# tm7_revB.net
KiCad netlist of a schematic drawn in EAGLE
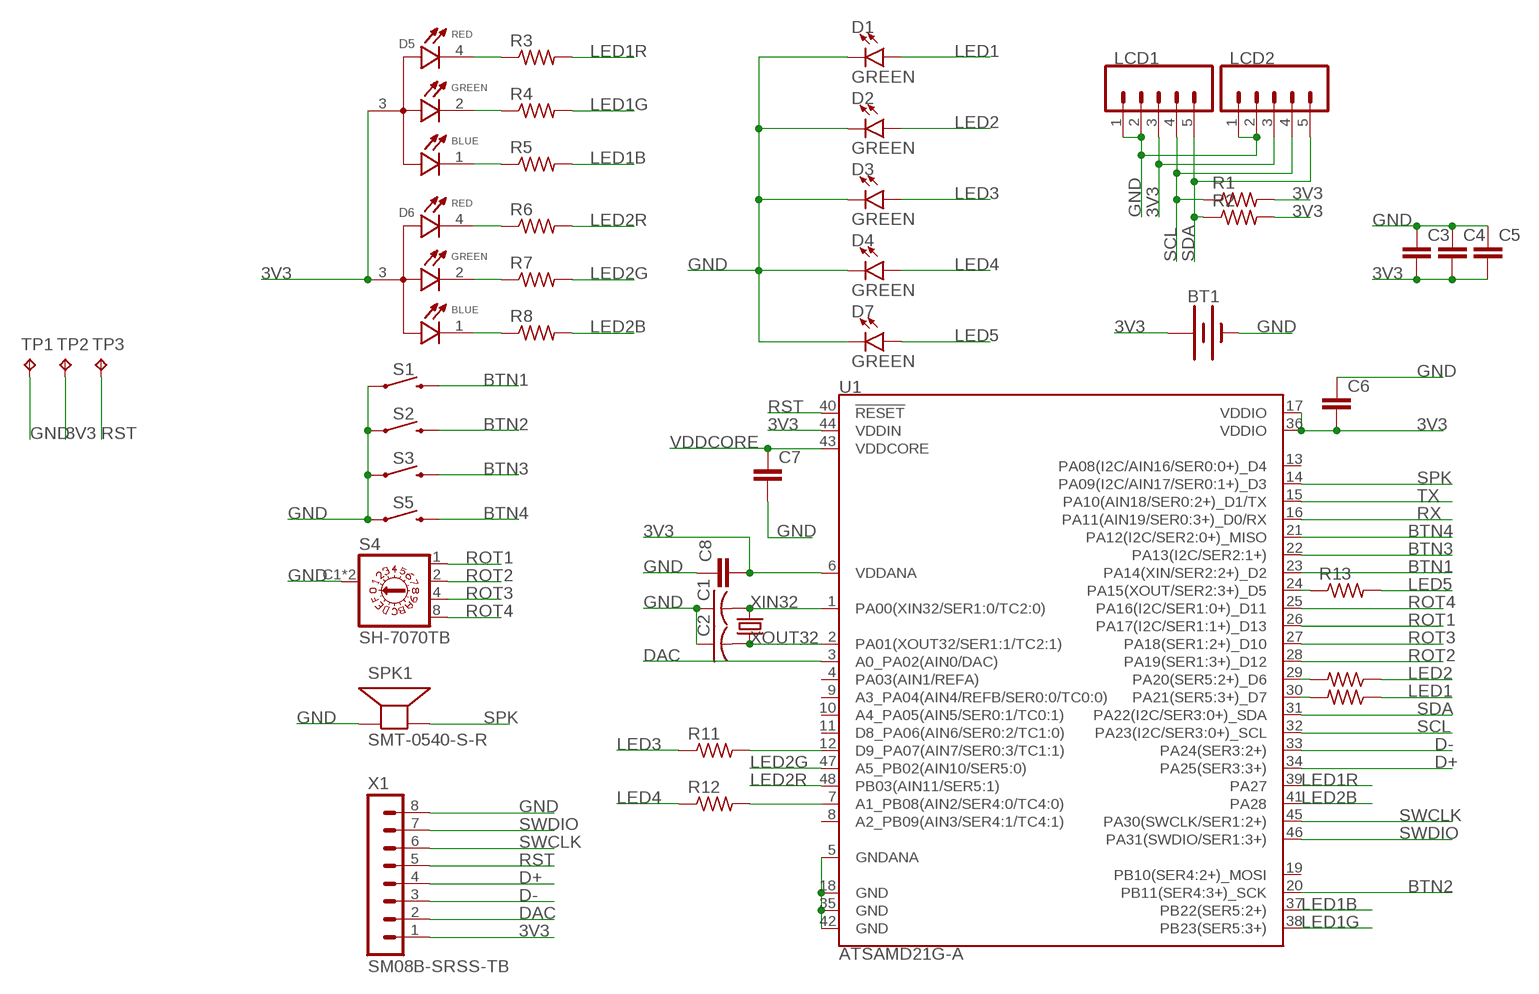
[diagram p0: schematic, sheet 1]

(export (version "E")
  (design (tool "Eeschema 10.0.6"))
  (components
    (comp (ref "BT1")
      (value "BATTERY-20MM_SMD_4LEGS_OVERPASTE_INNER")
      (footprint "eagle-import:BATTCON_20MM_4LEGS_OVERPASTE_INNER")
      (libsource (lib "eagle-import") (part "BATTERY-20MM_SMD_4LEGS_OVERPASTE_INNER"))
    )
    (comp (ref "C1")
      (value "C-USC0603")
      (footprint "eagle-import:C0603")
      (libsource (lib "eagle-import") (part "C-USC0603"))
    )
    (comp (ref "C2")
      (value "C-USC0603")
      (footprint "eagle-import:C0603")
      (libsource (lib "eagle-import") (part "C-USC0603"))
    )
    (comp (ref "C3")
      (value "C-EUC0603")
      (footprint "eagle-import:C0603")
      (libsource (lib "eagle-import") (part "C-EUC0603"))
    )
    (comp (ref "C4")
      (value "C-EUC0603")
      (footprint "eagle-import:C0603")
      (libsource (lib "eagle-import") (part "C-EUC0603"))
    )
    (comp (ref "C5")
      (value "C-EUC0603")
      (footprint "eagle-import:C0603")
      (libsource (lib "eagle-import") (part "C-EUC0603"))
    )
    (comp (ref "C6")
      (value "C-EUC0603")
      (footprint "eagle-import:C0603")
      (libsource (lib "eagle-import") (part "C-EUC0603"))
    )
    (comp (ref "C7")
      (value "C-EUC0603")
      (footprint "eagle-import:C0603")
      (libsource (lib "eagle-import") (part "C-EUC0603"))
    )
    (comp (ref "C8")
      (value "C-EUC0603")
      (footprint "eagle-import:C0603")
      (libsource (lib "eagle-import") (part "C-EUC0603"))
    )
    (comp (ref "D1")
      (value "GREEN")
      (footprint "eagle-import:LED-1206")
      (libsource (lib "eagle-import") (part "LED-GREEN1206"))
    )
    (comp (ref "D2")
      (value "GREEN")
      (footprint "eagle-import:LED-1206")
      (libsource (lib "eagle-import") (part "LED-GREEN1206"))
    )
    (comp (ref "D3")
      (value "GREEN")
      (footprint "eagle-import:LED-1206")
      (libsource (lib "eagle-import") (part "LED-GREEN1206"))
    )
    (comp (ref "D4")
      (value "GREEN")
      (footprint "eagle-import:LED-1206")
      (libsource (lib "eagle-import") (part "LED-GREEN1206"))
    )
    (comp (ref "D5")
      (value "EAST1616RGBA3")
      (footprint "eagle-import:LED_EAST1616RGBA3")
      (fields (field (name "MF") "Everlight Electronics"))
      (libsource (lib "eagle-import") (part "EAST1616RGBA3"))
    )
    (comp (ref "D6")
      (value "EAST1616RGBA3")
      (footprint "eagle-import:LED_EAST1616RGBA3")
      (fields (field (name "MF") "Everlight Electronics"))
      (libsource (lib "eagle-import") (part "EAST1616RGBA3"))
    )
    (comp (ref "D7")
      (value "GREEN")
      (footprint "eagle-import:LED-1206")
      (libsource (lib "eagle-import") (part "LED-GREEN1206"))
    )
    (comp (ref "LCD1")
      (value "CONN_05VERT_FEMALE_HEADER")
      (footprint "eagle-import:1X05_SMD_VERTICAL_COMBO")
      (libsource (lib "eagle-import") (part "CONN_05VERT_FEMALE_HEADER"))
    )
    (comp (ref "LCD2")
      (value "CONN_05VERT_FEMALE_HEADER")
      (footprint "eagle-import:1X05_SMD_VERTICAL_COMBO")
      (libsource (lib "eagle-import") (part "CONN_05VERT_FEMALE_HEADER"))
    )
    (comp (ref "R1")
      (value "R-US_R0603")
      (footprint "eagle-import:R0603")
      (libsource (lib "eagle-import") (part "R-US_R0603"))
    )
    (comp (ref "R2")
      (value "R-US_R0603")
      (footprint "eagle-import:R0603")
      (libsource (lib "eagle-import") (part "R-US_R0603"))
    )
    (comp (ref "R3")
      (value "R-US_R0603")
      (footprint "eagle-import:R0603")
      (libsource (lib "eagle-import") (part "R-US_R0603"))
    )
    (comp (ref "R4")
      (value "R-US_R0603")
      (footprint "eagle-import:R0603")
      (libsource (lib "eagle-import") (part "R-US_R0603"))
    )
    (comp (ref "R5")
      (value "R-US_R0603")
      (footprint "eagle-import:R0603")
      (libsource (lib "eagle-import") (part "R-US_R0603"))
    )
    (comp (ref "R6")
      (value "R-US_R0603")
      (footprint "eagle-import:R0603")
      (libsource (lib "eagle-import") (part "R-US_R0603"))
    )
    (comp (ref "R7")
      (value "R-US_R0603")
      (footprint "eagle-import:R0603")
      (libsource (lib "eagle-import") (part "R-US_R0603"))
    )
    (comp (ref "R8")
      (value "R-US_R0603")
      (footprint "eagle-import:R0603")
      (libsource (lib "eagle-import") (part "R-US_R0603"))
    )
    (comp (ref "R9")
      (value "R-US_R0603")
      (footprint "eagle-import:R0603")
      (libsource (lib "eagle-import") (part "R-US_R0603"))
    )
    (comp (ref "R10")
      (value "R-US_R0603")
      (footprint "eagle-import:R0603")
      (libsource (lib "eagle-import") (part "R-US_R0603"))
    )
    (comp (ref "R11")
      (value "R-US_R0603")
      (footprint "eagle-import:R0603")
      (libsource (lib "eagle-import") (part "R-US_R0603"))
    )
    (comp (ref "R12")
      (value "R-US_R0603")
      (footprint "eagle-import:R0603")
      (libsource (lib "eagle-import") (part "R-US_R0603"))
    )
    (comp (ref "R13")
      (value "R-US_R0603")
      (footprint "eagle-import:R0603")
      (libsource (lib "eagle-import") (part "R-US_R0603"))
    )
    (comp (ref "S1")
      (value "MOMENTARY-SWITCH-SPST-SMD-6.0X3.5MM")
      (footprint "eagle-import:TACTILE_SWITCH_SMD_6.0X3.5MM")
      (libsource (lib "eagle-import") (part "MOMENTARY-SWITCH-SPST-SMD-6.0X3.5MM"))
    )
    (comp (ref "S2")
      (value "MOMENTARY-SWITCH-SPST-SMD-6.0X3.5MM")
      (footprint "eagle-import:TACTILE_SWITCH_SMD_6.0X3.5MM")
      (libsource (lib "eagle-import") (part "MOMENTARY-SWITCH-SPST-SMD-6.0X3.5MM"))
    )
    (comp (ref "S3")
      (value "MOMENTARY-SWITCH-SPST-SMD-6.0X3.5MM")
      (footprint "eagle-import:TACTILE_SWITCH_SMD_6.0X3.5MM")
      (libsource (lib "eagle-import") (part "MOMENTARY-SWITCH-SPST-SMD-6.0X3.5MM"))
    )
    (comp (ref "S4")
      (value "SH-7070TB")
      (footprint "eagle-import:SH-7070B")
      (fields (field (name "MF") "Nidec Copal"))
      (libsource (lib "eagle-import") (part "SH-7070TB"))
    )
    (comp (ref "S5")
      (value "MOMENTARY-SWITCH-SPST-SMD-6.0X3.5MM")
      (footprint "eagle-import:TACTILE_SWITCH_SMD_6.0X3.5MM")
      (libsource (lib "eagle-import") (part "MOMENTARY-SWITCH-SPST-SMD-6.0X3.5MM"))
    )
    (comp (ref "SPK1")
      (value "SMT-0540-S-R")
      (footprint "eagle-import:SMT-0540-S-R")
      (fields (field (name "MF") "PUI"))
      (libsource (lib "eagle-import") (part "SMT-0540-S-R"))
    )
    (comp (ref "TP1")
      (value "TPTP12R")
      (footprint "eagle-import:TP12R")
      (libsource (lib "eagle-import") (part "TPTP12R"))
    )
    (comp (ref "TP2")
      (value "TPTP12R")
      (footprint "eagle-import:TP12R")
      (libsource (lib "eagle-import") (part "TPTP12R"))
    )
    (comp (ref "TP3")
      (value "TPTP12R")
      (footprint "eagle-import:TP12R")
      (libsource (lib "eagle-import") (part "TPTP12R"))
    )
    (comp (ref "U1")
      (value "ATSAMD21G-A")
      (footprint "eagle-import:TQFP-48")
      (libsource (lib "eagle-import") (part "ATSAMD21G-A"))
    )
    (comp (ref "X1")
      (value "SM08B-SRSS-TB")
      (footprint "eagle-import:SM08B-SRSS-TB")
      (libsource (lib "eagle-import") (part "SM08B-SRSS-TB"))
    )
    (comp (ref "Y1")
      (value "32.768kHz")
      (footprint "eagle-import:CRYSTAL-SMD-3.2X1.5MM")
      (libsource (lib "eagle-import") (part "CRYSTAL-32.768KHZSMD-3.2X1.5"))
    )
  )
  (nets
    (net (code "1") (name "/3V3") (class "Default")
      (node (ref "BT1") (pin "1") (pinfunction "+_1") (pintype "power_in"))
      (node (ref "C3") (pin "2") (pinfunction "2_2") (pintype "passive"))
      (node (ref "C4") (pin "2") (pinfunction "2_2") (pintype "passive"))
      (node (ref "C5") (pin "2") (pinfunction "2_2") (pintype "passive"))
      (node (ref "C6") (pin "2") (pinfunction "2_2") (pintype "passive"))
      (node (ref "C8") (pin "2") (pinfunction "2_2") (pintype "passive"))
      (node (ref "D5") (pin "3") (pinfunction "A_3") (pintype "passive"))
      (node (ref "D6") (pin "3") (pinfunction "A_3") (pintype "passive"))
      (node (ref "LCD1") (pin "3") (pinfunction "3_3") (pintype "passive"))
      (node (ref "LCD2") (pin "3") (pinfunction "3_3") (pintype "passive"))
      (node (ref "R1") (pin "2") (pinfunction "2_2") (pintype "passive"))
      (node (ref "R2") (pin "2") (pinfunction "2_2") (pintype "passive"))
      (node (ref "TP2") (pin "TP") (pinfunction "TP_TP") (pintype "input"))
      (node (ref "U1") (pin "17") (pinfunction "VDDIO_17") (pintype "bidirectional"))
      (node (ref "U1") (pin "36") (pinfunction "VDDIO_36") (pintype "bidirectional"))
      (node (ref "U1") (pin "44") (pinfunction "VDDIN_44") (pintype "bidirectional"))
      (node (ref "U1") (pin "6") (pinfunction "VDDANA_6") (pintype "bidirectional"))
      (node (ref "X1") (pin "1") (pinfunction "1_1") (pintype "passive"))
    )
    (net (code "2") (name "/BTN1") (class "Default")
      (node (ref "S1") (pin "2") (pinfunction "2_2") (pintype "passive"))
      (node (ref "U1") (pin "23") (pinfunction "PA14(XIN/SER2:2+)_D2_23") (pintype "bidirectional"))
    )
    (net (code "3") (name "/BTN2") (class "Default")
      (node (ref "S2") (pin "2") (pinfunction "2_2") (pintype "passive"))
      (node (ref "U1") (pin "20") (pinfunction "PB11(SER4:3+)_SCK_20") (pintype "bidirectional"))
    )
    (net (code "4") (name "/BTN3") (class "Default")
      (node (ref "S3") (pin "2") (pinfunction "2_2") (pintype "passive"))
      (node (ref "U1") (pin "22") (pinfunction "PA13(I2C/SER2:1+)_22") (pintype "bidirectional"))
    )
    (net (code "5") (name "/BTN4") (class "Default")
      (node (ref "S5") (pin "2") (pinfunction "2_2") (pintype "passive"))
      (node (ref "U1") (pin "21") (pinfunction "PA12(I2C/SER2:0+)_MISO_21") (pintype "bidirectional"))
    )
    (net (code "6") (name "/D+") (class "Default")
      (node (ref "U1") (pin "34") (pinfunction "PA25(SER3:3+)_34") (pintype "bidirectional"))
      (node (ref "X1") (pin "4") (pinfunction "4_4") (pintype "passive"))
    )
    (net (code "7") (name "/D-") (class "Default")
      (node (ref "U1") (pin "33") (pinfunction "PA24(SER3:2+)_33") (pintype "bidirectional"))
      (node (ref "X1") (pin "3") (pinfunction "3_3") (pintype "passive"))
    )
    (net (code "8") (name "/DAC") (class "Default")
      (node (ref "U1") (pin "3") (pinfunction "A0_PA02(AIN0/DAC)_3") (pintype "bidirectional"))
      (node (ref "X1") (pin "2") (pinfunction "2_2") (pintype "passive"))
    )
    (net (code "9") (name "/GND") (class "Default")
      (node (ref "BT1") (pin "2") (pinfunction "-_2") (pintype "power_in"))
      (node (ref "C1") (pin "1") (pinfunction "1_1") (pintype "passive"))
      (node (ref "C2") (pin "1") (pinfunction "1_1") (pintype "passive"))
      (node (ref "C3") (pin "1") (pinfunction "1_1") (pintype "passive"))
      (node (ref "C4") (pin "1") (pinfunction "1_1") (pintype "passive"))
      (node (ref "C5") (pin "1") (pinfunction "1_1") (pintype "passive"))
      (node (ref "C6") (pin "1") (pinfunction "1_1") (pintype "passive"))
      (node (ref "C7") (pin "2") (pinfunction "2_2") (pintype "passive"))
      (node (ref "C8") (pin "1") (pinfunction "1_1") (pintype "passive"))
      (node (ref "D1") (pin "C") (pinfunction "C_C") (pintype "passive"))
      (node (ref "D2") (pin "C") (pinfunction "C_C") (pintype "passive"))
      (node (ref "D3") (pin "C") (pinfunction "C_C") (pintype "passive"))
      (node (ref "D4") (pin "C") (pinfunction "C_C") (pintype "passive"))
      (node (ref "D7") (pin "C") (pinfunction "C_C") (pintype "passive"))
      (node (ref "LCD1") (pin "1") (pinfunction "1_1") (pintype "passive"))
      (node (ref "LCD1") (pin "2") (pinfunction "2_2") (pintype "passive"))
      (node (ref "LCD2") (pin "1") (pinfunction "1_1") (pintype "passive"))
      (node (ref "LCD2") (pin "2") (pinfunction "2_2") (pintype "passive"))
      (node (ref "S1") (pin "1") (pinfunction "1_1") (pintype "passive"))
      (node (ref "S2") (pin "1") (pinfunction "1_1") (pintype "passive"))
      (node (ref "S3") (pin "1") (pinfunction "1_1") (pintype "passive"))
      (node (ref "S4") (pin "C1") (pinfunction "C_C1") (pintype "passive"))
      (node (ref "S4") (pin "C2") (pinfunction "C_C2") (pintype "passive"))
      (node (ref "S5") (pin "1") (pinfunction "1_1") (pintype "passive"))
      (node (ref "SPK1") (pin "-") (pinfunction "+_-") (pintype "passive"))
      (node (ref "TP1") (pin "TP") (pinfunction "TP_TP") (pintype "input"))
      (node (ref "U1") (pin "18") (pinfunction "GND_18") (pintype "bidirectional"))
      (node (ref "U1") (pin "35") (pinfunction "GND_35") (pintype "bidirectional"))
      (node (ref "U1") (pin "42") (pinfunction "GND_42") (pintype "bidirectional"))
      (node (ref "U1") (pin "5") (pinfunction "GNDANA_5") (pintype "bidirectional"))
      (node (ref "X1") (pin "8") (pinfunction "8_8") (pintype "passive"))
    )
    (net (code "10") (name "/LED1") (class "Default")
      (node (ref "D1") (pin "A") (pinfunction "A_A") (pintype "passive"))
      (node (ref "R9") (pin "1") (pinfunction "1_1") (pintype "passive"))
    )
    (net (code "11") (name "/LED1B") (class "Default")
      (node (ref "R5") (pin "2") (pinfunction "2_2") (pintype "passive"))
      (node (ref "U1") (pin "37") (pinfunction "PB22(SER5:2+)_37") (pintype "bidirectional"))
    )
    (net (code "12") (name "/LED1G") (class "Default")
      (node (ref "R4") (pin "2") (pinfunction "2_2") (pintype "passive"))
      (node (ref "U1") (pin "38") (pinfunction "PB23(SER5:3+)_38") (pintype "bidirectional"))
    )
    (net (code "13") (name "/LED1R") (class "Default")
      (node (ref "R3") (pin "2") (pinfunction "2_2") (pintype "passive"))
      (node (ref "U1") (pin "39") (pinfunction "PA27_39") (pintype "bidirectional"))
    )
    (net (code "14") (name "/LED2") (class "Default")
      (node (ref "D2") (pin "A") (pinfunction "A_A") (pintype "passive"))
      (node (ref "R10") (pin "1") (pinfunction "1_1") (pintype "passive"))
    )
    (net (code "15") (name "/LED2B") (class "Default")
      (node (ref "R8") (pin "2") (pinfunction "2_2") (pintype "passive"))
      (node (ref "U1") (pin "41") (pinfunction "PA28_41") (pintype "bidirectional"))
    )
    (net (code "16") (name "/LED2G") (class "Default")
      (node (ref "R7") (pin "2") (pinfunction "2_2") (pintype "passive"))
      (node (ref "U1") (pin "47") (pinfunction "A5_PB02(AIN10/SER5:0)_47") (pintype "bidirectional"))
    )
    (net (code "17") (name "/LED2R") (class "Default")
      (node (ref "R6") (pin "2") (pinfunction "2_2") (pintype "passive"))
      (node (ref "U1") (pin "48") (pinfunction "PB03(AIN11/SER5:1)_48") (pintype "bidirectional"))
    )
    (net (code "18") (name "/LED3") (class "Default")
      (node (ref "D3") (pin "A") (pinfunction "A_A") (pintype "passive"))
      (node (ref "R11") (pin "1") (pinfunction "1_1") (pintype "passive"))
    )
    (net (code "19") (name "/LED4") (class "Default")
      (node (ref "D4") (pin "A") (pinfunction "A_A") (pintype "passive"))
      (node (ref "R12") (pin "1") (pinfunction "1_1") (pintype "passive"))
    )
    (net (code "20") (name "/LED5") (class "Default")
      (node (ref "D7") (pin "A") (pinfunction "A_A") (pintype "passive"))
      (node (ref "R13") (pin "2") (pinfunction "2_2") (pintype "passive"))
    )
    (net (code "21") (name "/ROT1") (class "Default")
      (node (ref "S4") (pin "1") (pinfunction "1_1") (pintype "passive"))
      (node (ref "U1") (pin "26") (pinfunction "PA17(I2C/SER1:1+)_D13_26") (pintype "bidirectional"))
    )
    (net (code "22") (name "/ROT2") (class "Default")
      (node (ref "S4") (pin "2") (pinfunction "2_2") (pintype "passive"))
      (node (ref "U1") (pin "28") (pinfunction "PA19(SER1:3+)_D12_28") (pintype "bidirectional"))
    )
    (net (code "23") (name "/ROT3") (class "Default")
      (node (ref "S4") (pin "4") (pinfunction "4_4") (pintype "passive"))
      (node (ref "U1") (pin "27") (pinfunction "PA18(SER1:2+)_D10_27") (pintype "bidirectional"))
    )
    (net (code "24") (name "/ROT4") (class "Default")
      (node (ref "S4") (pin "8") (pinfunction "8_8") (pintype "passive"))
      (node (ref "U1") (pin "25") (pinfunction "PA16(I2C/SER1:0+)_D11_25") (pintype "bidirectional"))
    )
    (net (code "25") (name "/RST") (class "Default")
      (node (ref "TP3") (pin "TP") (pinfunction "TP_TP") (pintype "input"))
      (node (ref "U1") (pin "40") (pinfunction "~{RESET}_40") (pintype "bidirectional"))
      (node (ref "X1") (pin "5") (pinfunction "5_5") (pintype "passive"))
    )
    (net (code "26") (name "/RX") (class "Default")
      (node (ref "U1") (pin "16") (pinfunction "PA11(AIN19/SER0:3+)_D0/RX_16") (pintype "bidirectional"))
    )
    (net (code "27") (name "/SCL") (class "Default")
      (node (ref "LCD1") (pin "4") (pinfunction "4_4") (pintype "passive"))
      (node (ref "LCD2") (pin "4") (pinfunction "4_4") (pintype "passive"))
      (node (ref "R1") (pin "1") (pinfunction "1_1") (pintype "passive"))
      (node (ref "U1") (pin "32") (pinfunction "PA23(I2C/SER3:0+)_SCL_32") (pintype "bidirectional"))
    )
    (net (code "28") (name "/SDA") (class "Default")
      (node (ref "LCD1") (pin "5") (pinfunction "5_5") (pintype "passive"))
      (node (ref "LCD2") (pin "5") (pinfunction "5_5") (pintype "passive"))
      (node (ref "R2") (pin "1") (pinfunction "1_1") (pintype "passive"))
      (node (ref "U1") (pin "31") (pinfunction "PA22(I2C/SER3:0+)_SDA_31") (pintype "bidirectional"))
    )
    (net (code "29") (name "/SPK") (class "Default")
      (node (ref "SPK1") (pin "+") (pinfunction "-_+") (pintype "passive"))
      (node (ref "U1") (pin "14") (pinfunction "PA09(I2C/AIN17/SER0:1+)_D3_14") (pintype "bidirectional"))
    )
    (net (code "30") (name "/SWCLK") (class "Default")
      (node (ref "U1") (pin "45") (pinfunction "PA30(SWCLK/SER1:2+)_45") (pintype "bidirectional"))
      (node (ref "X1") (pin "6") (pinfunction "6_6") (pintype "passive"))
    )
    (net (code "31") (name "/SWDIO") (class "Default")
      (node (ref "U1") (pin "46") (pinfunction "PA31(SWDIO/SER1:3+)_46") (pintype "bidirectional"))
      (node (ref "X1") (pin "7") (pinfunction "7_7") (pintype "passive"))
    )
    (net (code "32") (name "/TX") (class "Default")
      (node (ref "U1") (pin "15") (pinfunction "PA10(AIN18/SER0:2+)_D1/TX_15") (pintype "bidirectional"))
    )
    (net (code "33") (name "/VDDCORE") (class "Default")
      (node (ref "C7") (pin "1") (pinfunction "1_1") (pintype "passive"))
      (node (ref "U1") (pin "43") (pinfunction "VDDCORE_43") (pintype "bidirectional"))
    )
    (net (code "34") (name "/XIN32") (class "Default")
      (node (ref "C1") (pin "2") (pinfunction "2_2") (pintype "passive"))
      (node (ref "U1") (pin "1") (pinfunction "PA00(XIN32/SER1:0/TC2:0)_1") (pintype "bidirectional"))
      (node (ref "Y1") (pin "P$2") (pinfunction "2_P$2") (pintype "passive"))
    )
    (net (code "35") (name "/XOUT32") (class "Default")
      (node (ref "C2") (pin "2") (pinfunction "2_2") (pintype "passive"))
      (node (ref "U1") (pin "2") (pinfunction "PA01(XOUT32/SER1:1/TC2:1)_2") (pintype "bidirectional"))
      (node (ref "Y1") (pin "P$1") (pinfunction "1_P$1") (pintype "passive"))
    )
    (net (code "36") (name "Net-(D5-B_C)") (class "Default")
      (node (ref "D5") (pin "1") (pinfunction "B_C_1") (pintype "passive"))
      (node (ref "R5") (pin "1") (pinfunction "1_1") (pintype "passive"))
    )
    (net (code "37") (name "Net-(D5-G_C)") (class "Default")
      (node (ref "D5") (pin "2") (pinfunction "G_C_2") (pintype "passive"))
      (node (ref "R4") (pin "1") (pinfunction "1_1") (pintype "passive"))
    )
    (net (code "38") (name "Net-(D5-R_C)") (class "Default")
      (node (ref "D5") (pin "4") (pinfunction "R_C_4") (pintype "passive"))
      (node (ref "R3") (pin "1") (pinfunction "1_1") (pintype "passive"))
    )
    (net (code "39") (name "Net-(D6-B_C)") (class "Default")
      (node (ref "D6") (pin "1") (pinfunction "B_C_1") (pintype "passive"))
      (node (ref "R8") (pin "1") (pinfunction "1_1") (pintype "passive"))
    )
    (net (code "40") (name "Net-(D6-G_C)") (class "Default")
      (node (ref "D6") (pin "2") (pinfunction "G_C_2") (pintype "passive"))
      (node (ref "R7") (pin "1") (pinfunction "1_1") (pintype "passive"))
    )
    (net (code "41") (name "Net-(D6-R_C)") (class "Default")
      (node (ref "D6") (pin "4") (pinfunction "R_C_4") (pintype "passive"))
      (node (ref "R6") (pin "1") (pinfunction "1_1") (pintype "passive"))
    )
    (net (code "42") (name "Net-(U1-A1_PB08(AIN2{slash}SER4:0{slash}TC4:0))") (class "Default")
      (node (ref "R12") (pin "2") (pinfunction "2_2") (pintype "passive"))
      (node (ref "U1") (pin "7") (pinfunction "A1_PB08(AIN2/SER4:0/TC4:0)_7") (pintype "bidirectional"))
    )
    (net (code "43") (name "Net-(U1-D9_PA07(AIN7{slash}SER0:3{slash}TC1:1))") (class "Default")
      (node (ref "R11") (pin "2") (pinfunction "2_2") (pintype "passive"))
      (node (ref "U1") (pin "12") (pinfunction "D9_PA07(AIN7/SER0:3/TC1:1)_12") (pintype "bidirectional"))
    )
    (net (code "44") (name "Net-(U1-PA15(XOUT{slash}SER2:3+)_D5)") (class "Default")
      (node (ref "R13") (pin "1") (pinfunction "1_1") (pintype "passive"))
      (node (ref "U1") (pin "24") (pinfunction "PA15(XOUT/SER2:3+)_D5_24") (pintype "bidirectional"))
    )
    (net (code "45") (name "Net-(U1-PA20(SER5:2+)_D6)") (class "Default")
      (node (ref "R10") (pin "2") (pinfunction "2_2") (pintype "passive"))
      (node (ref "U1") (pin "29") (pinfunction "PA20(SER5:2+)_D6_29") (pintype "bidirectional"))
    )
    (net (code "46") (name "Net-(U1-PA21(SER5:3+)_D7)") (class "Default")
      (node (ref "R9") (pin "2") (pinfunction "2_2") (pintype "passive"))
      (node (ref "U1") (pin "30") (pinfunction "PA21(SER5:3+)_D7_30") (pintype "bidirectional"))
    )
    (net (code "47") (name "unconnected-(U1-A2_PB09(AIN3{slash}SER4:1{slash}TC4:1)-Pad8)") (class "Default")
      (node (ref "U1") (pin "8") (pinfunction "A2_PB09(AIN3/SER4:1/TC4:1)_8") (pintype "bidirectional"))
    )
    (net (code "48") (name "unconnected-(U1-A3_PA04(AIN4{slash}REFB{slash}SER0:0{slash}TC0:0)-Pad9)") (class "Default")
      (node (ref "U1") (pin "9") (pinfunction "A3_PA04(AIN4/REFB/SER0:0/TC0:0)_9") (pintype "bidirectional"))
    )
    (net (code "49") (name "unconnected-(U1-A4_PA05(AIN5{slash}SER0:1{slash}TC0:1)-Pad10)") (class "Default")
      (node (ref "U1") (pin "10") (pinfunction "A4_PA05(AIN5/SER0:1/TC0:1)_10") (pintype "bidirectional"))
    )
    (net (code "50") (name "unconnected-(U1-D8_PA06(AIN6{slash}SER0:2{slash}TC1:0)-Pad11)") (class "Default")
      (node (ref "U1") (pin "11") (pinfunction "D8_PA06(AIN6/SER0:2/TC1:0)_11") (pintype "bidirectional"))
    )
    (net (code "51") (name "unconnected-(U1-PA03(AIN1{slash}REFA)-Pad4)") (class "Default")
      (node (ref "U1") (pin "4") (pinfunction "PA03(AIN1/REFA)_4") (pintype "bidirectional"))
    )
    (net (code "52") (name "unconnected-(U1-PA08(I2C{slash}AIN16{slash}SER0:0+)_D4-Pad13)") (class "Default")
      (node (ref "U1") (pin "13") (pinfunction "PA08(I2C/AIN16/SER0:0+)_D4_13") (pintype "bidirectional"))
    )
    (net (code "53") (name "unconnected-(U1-PB10(SER4:2+)_MOSI-Pad19)") (class "Default")
      (node (ref "U1") (pin "19") (pinfunction "PB10(SER4:2+)_MOSI_19") (pintype "bidirectional"))
    )
  )
)
